# sensortag_motherboard_v004.net
KiCad netlist of a schematic drawn in EAGLE
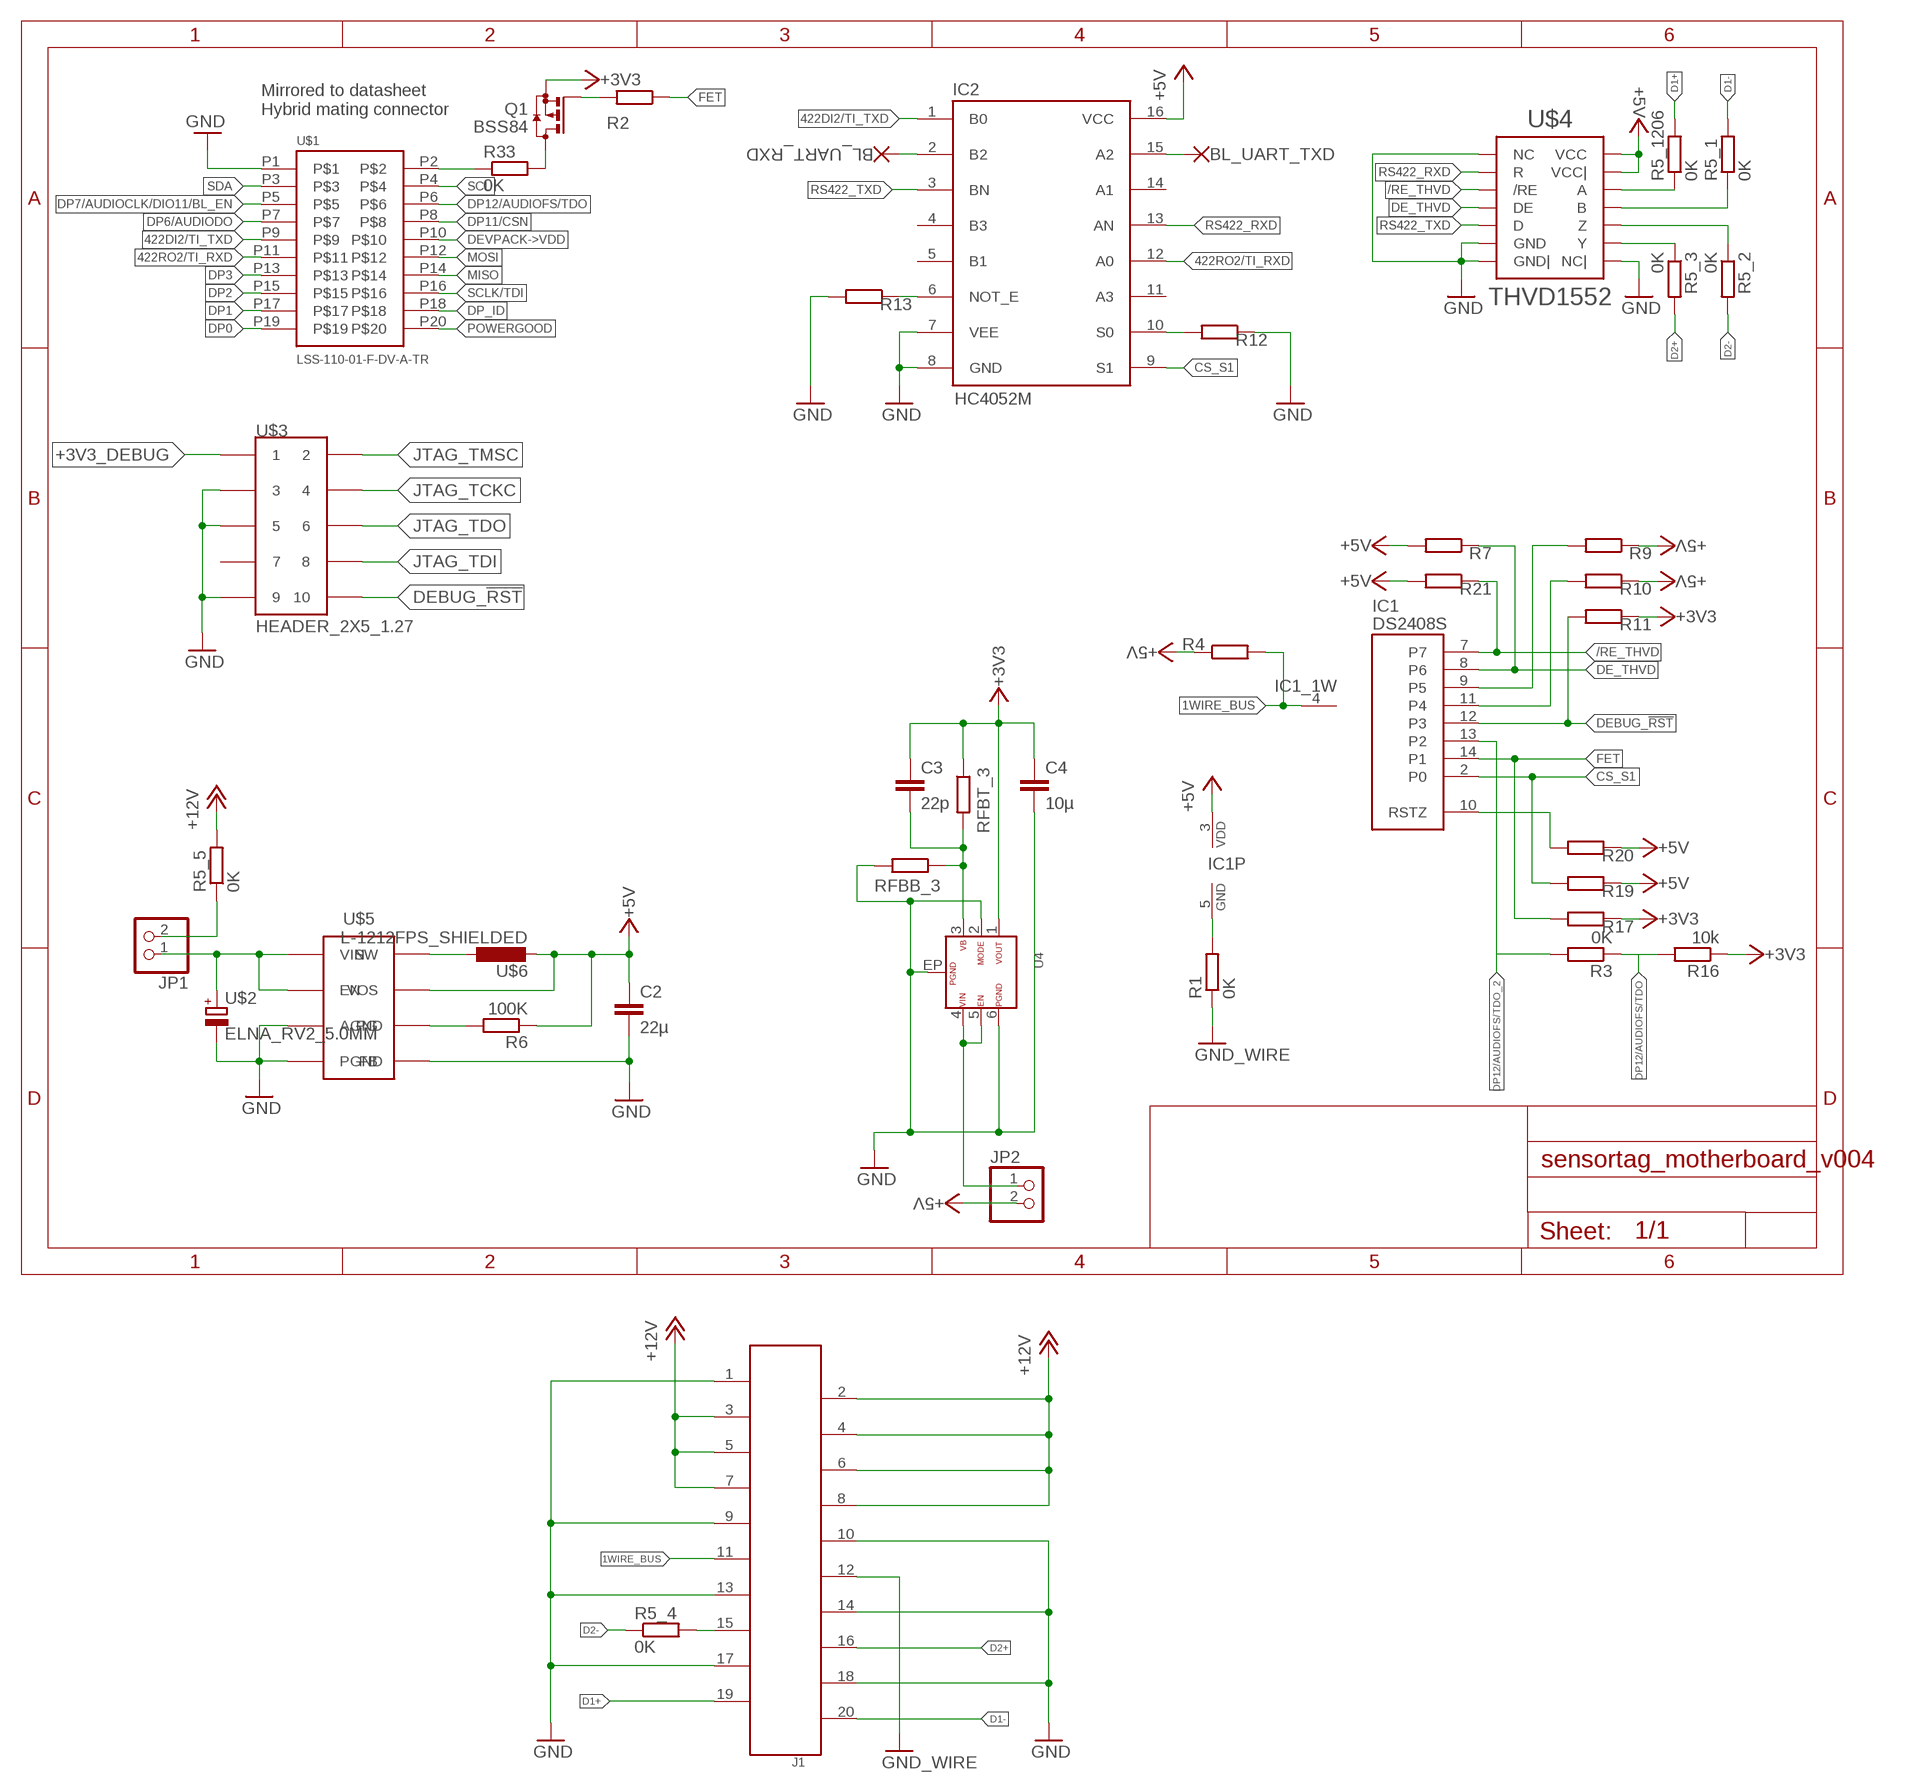
[diagram p0: schematic, sheet 1]

(export (version "E")
  (design (tool "Eeschema 10.0.6"))
  (components
    (comp (ref "BL_UART_RXD")
      (value "WIREPADSMD1,27-254")
      (footprint "eagle-import:SMD1,27-2,54")
      (libsource (lib "eagle-import") (part "WIREPADSMD1,27-254"))
    )
    (comp (ref "BL_UART_TXD")
      (value "WIREPADSMD1,27-254")
      (footprint "eagle-import:SMD1,27-2,54")
      (libsource (lib "eagle-import") (part "WIREPADSMD1,27-254"))
    )
    (comp (ref "C2")
      (value "22µ")
      (footprint "eagle-import:C1206")
      (libsource (lib "eagle-import") (part "C-EUC1206"))
    )
    (comp (ref "C3")
      (value "22p")
      (footprint "eagle-import:C0402")
      (libsource (lib "eagle-import") (part "C-EUC0402"))
    )
    (comp (ref "C4")
      (value "10µ")
      (footprint "eagle-import:C0603")
      (libsource (lib "eagle-import") (part "C-EUC0603"))
    )
    (comp (ref "IC1")
      (value "DS2408S")
      (footprint "eagle-import:SO16")
      (libsource (lib "eagle-import") (part "DS2408S"))
    )
    (comp (ref "IC2")
      (value "HC4052M")
      (footprint "eagle-import:SO16")
      (libsource (lib "eagle-import") (part "HC4052M"))
    )
    (comp (ref "J1")
      (value "490107672012")
      (footprint "eagle-import:490107672012")
      (libsource (lib "eagle-import") (part "490107672012"))
    )
    (comp (ref "JP1")
      (value "PINHD-1X2")
      (footprint "eagle-import:1X02")
      (libsource (lib "eagle-import") (part "PINHD-1X2"))
    )
    (comp (ref "JP2")
      (value "PINHD-1X2")
      (footprint "eagle-import:1X02")
      (libsource (lib "eagle-import") (part "PINHD-1X2"))
    )
    (comp (ref "Q1")
      (value "BSS84")
      (footprint "eagle-import:SOT23")
      (libsource (lib "eagle-import") (part "BSS84"))
    )
    (comp (ref "R1")
      (value "0K")
      (footprint "eagle-import:R0603")
      (libsource (lib "eagle-import") (part "R-EU_R0603"))
    )
    (comp (ref "R2")
      (value "100")
      (footprint "eagle-import:R0402")
      (libsource (lib "eagle-import") (part "R0402"))
    )
    (comp (ref "R3")
      (value "0K")
      (footprint "eagle-import:R0603")
      (libsource (lib "eagle-import") (part "R-EU_R0603"))
    )
    (comp (ref "R4")
      (value "10k")
      (footprint "eagle-import:R0402")
      (libsource (lib "eagle-import") (part "R0402"))
    )
    (comp (ref "R5_1")
      (value "0K")
      (footprint "eagle-import:R1206")
      (libsource (lib "eagle-import") (part "R-EU_R1206"))
    )
    (comp (ref "R5_2")
      (value "0K")
      (footprint "eagle-import:R1206")
      (libsource (lib "eagle-import") (part "R-EU_R1206"))
    )
    (comp (ref "R5_3")
      (value "0K")
      (footprint "eagle-import:R1206")
      (libsource (lib "eagle-import") (part "R-EU_R1206"))
    )
    (comp (ref "R5_4")
      (value "0K")
      (footprint "eagle-import:R1206")
      (libsource (lib "eagle-import") (part "R-EU_R1206"))
    )
    (comp (ref "R5_5")
      (value "0K")
      (footprint "eagle-import:R1206")
      (libsource (lib "eagle-import") (part "R-EU_R1206"))
    )
    (comp (ref "R5_1206")
      (value "0K")
      (footprint "eagle-import:R1206")
      (libsource (lib "eagle-import") (part "R-EU_R1206"))
    )
    (comp (ref "R6")
      (value "100K")
      (footprint "eagle-import:R0603")
      (libsource (lib "eagle-import") (part "R-EU_R0603"))
    )
    (comp (ref "R7")
      (value "10k")
      (footprint "eagle-import:R0402")
      (libsource (lib "eagle-import") (part "R0402"))
    )
    (comp (ref "R9")
      (value "10k")
      (footprint "eagle-import:R0402")
      (libsource (lib "eagle-import") (part "R0402"))
    )
    (comp (ref "R10")
      (value "10k")
      (footprint "eagle-import:R0402")
      (libsource (lib "eagle-import") (part "R0402"))
    )
    (comp (ref "R11")
      (value "10k")
      (footprint "eagle-import:R0402")
      (libsource (lib "eagle-import") (part "R0402"))
    )
    (comp (ref "R12")
      (value "10k")
      (footprint "eagle-import:R0402")
      (libsource (lib "eagle-import") (part "R0402"))
    )
    (comp (ref "R13")
      (value "10k")
      (footprint "eagle-import:R0402")
      (libsource (lib "eagle-import") (part "R0402"))
    )
    (comp (ref "R16")
      (value "10k")
      (footprint "eagle-import:R0402")
      (libsource (lib "eagle-import") (part "R0402"))
    )
    (comp (ref "R17")
      (value "10k")
      (footprint "eagle-import:R0402")
      (libsource (lib "eagle-import") (part "R0402"))
    )
    (comp (ref "R19")
      (value "10k")
      (footprint "eagle-import:R0402")
      (libsource (lib "eagle-import") (part "R0402"))
    )
    (comp (ref "R20")
      (value "10k")
      (footprint "eagle-import:R0402")
      (libsource (lib "eagle-import") (part "R0402"))
    )
    (comp (ref "R21")
      (value "10k")
      (footprint "eagle-import:R0402")
      (libsource (lib "eagle-import") (part "R0402"))
    )
    (comp (ref "R33")
      (value "0K")
      (footprint "eagle-import:R0603")
      (libsource (lib "eagle-import") (part "R-EU_R0603"))
    )
    (comp (ref "RFBB_3")
      (value "22,1K")
      (footprint "eagle-import:R0402")
      (libsource (lib "eagle-import") (part "R0402"))
    )
    (comp (ref "RFBT_3")
      (value "100K")
      (footprint "eagle-import:R0402")
      (libsource (lib "eagle-import") (part "R0402"))
    )
    (comp (ref "U$1")
      (value "LSS-110-01-F-DV-A-TR")
      (footprint "eagle-import:LSS-110-01-F-DV-A-TR")
      (libsource (lib "eagle-import") (part "LSS-110-01-F-DV-A-TR"))
    )
    (comp (ref "U$2")
      (value "ELNA_RV2_5.0MM")
      (footprint "eagle-import:ELNA_RV2_5.0MM")
      (libsource (lib "eagle-import") (part "ELNA_RV2_5.0MM"))
    )
    (comp (ref "U$3")
      (value "HEADER_2X5_1.27")
      (footprint "eagle-import:HEADER_2X5_1.27")
      (libsource (lib "eagle-import") (part "HEADER_2X5_1.27"))
    )
    (comp (ref "U$4")
      (value "TVHD1552")
      (footprint "eagle-import:SO14")
      (libsource (lib "eagle-import") (part "TVHD1552"))
    )
    (comp (ref "U$5")
      (value "TPS62173")
      (footprint "eagle-import:WSON8")
      (libsource (lib "eagle-import") (part "TPS62173"))
    )
    (comp (ref "U$6")
      (value "L-1212FPS_SHIELDED")
      (footprint "eagle-import:L-1212FPS_SHIELDED")
      (libsource (lib "eagle-import") (part "L-1212FPS_SHIELDED"))
    )
    (comp (ref "U4")
      (value "VDMM_171960501")
      (footprint "eagle-import:VDMM_171960501")
      (libsource (lib "eagle-import") (part "VDMM_171960501"))
    )
  )
  (nets
    (net (code "1") (name "+3V3") (class "Default")
      (node (ref "C3") (pin "1") (pinfunction "1_1") (pintype "passive"))
      (node (ref "C4") (pin "1") (pinfunction "1_1") (pintype "passive"))
      (node (ref "Q1") (pin "2") (pinfunction "S_2") (pintype "passive"))
      (node (ref "R11") (pin "P$1") (pinfunction "1_P$1") (pintype "passive"))
      (node (ref "R16") (pin "P$1") (pinfunction "1_P$1") (pintype "passive"))
      (node (ref "R17") (pin "P$1") (pinfunction "1_P$1") (pintype "passive"))
      (node (ref "RFBT_3") (pin "P$1") (pinfunction "1_P$1") (pintype "passive"))
      (node (ref "U4") (pin "1") (pinfunction "VOUT_1") (pintype "output"))
    )
    (net (code "2") (name "+3V3_DEBUG") (class "Default")
      (node (ref "U$3") (pin "P$1") (pinfunction "1_P$1") (pintype "bidirectional"))
    )
    (net (code "3") (name "+5V") (class "Default")
      (node (ref "C2") (pin "1") (pinfunction "1_1") (pintype "passive"))
      (node (ref "IC1") (pin "3") (pinfunction "VDD_3") (pintype "power_in"))
      (node (ref "IC2") (pin "16") (pinfunction "VCC_16") (pintype "bidirectional"))
      (node (ref "JP2") (pin "2") (pinfunction "2_2") (pintype "passive"))
      (node (ref "R10") (pin "P$1") (pinfunction "1_P$1") (pintype "passive"))
      (node (ref "R19") (pin "P$1") (pinfunction "1_P$1") (pintype "passive"))
      (node (ref "R20") (pin "P$1") (pinfunction "1_P$1") (pintype "passive"))
      (node (ref "R21") (pin "P$2") (pinfunction "2_P$2") (pintype "passive"))
      (node (ref "R4") (pin "P$1") (pinfunction "1_P$1") (pintype "passive"))
      (node (ref "R6") (pin "1") (pinfunction "1_1") (pintype "passive"))
      (node (ref "R7") (pin "P$2") (pinfunction "2_P$2") (pintype "passive"))
      (node (ref "R9") (pin "P$1") (pinfunction "1_P$1") (pintype "passive"))
      (node (ref "U$4") (pin "13") (pinfunction "VCC|_13") (pintype "bidirectional"))
      (node (ref "U$4") (pin "14") (pinfunction "VCC_14") (pintype "bidirectional"))
      (node (ref "U$5") (pin "VOS") (pinfunction "VOS_VOS") (pintype "bidirectional"))
      (node (ref "U$6") (pin "P$2") (pinfunction "2_P$2") (pintype "passive"))
    )
    (net (code "4") (name "+12V") (class "Default")
      (node (ref "J1") (pin "2") (pinfunction "19_2") (pintype "passive"))
      (node (ref "J1") (pin "3") (pinfunction "18_3") (pintype "passive"))
      (node (ref "J1") (pin "4") (pinfunction "17_4") (pintype "passive"))
      (node (ref "J1") (pin "5") (pinfunction "16_5") (pintype "passive"))
      (node (ref "J1") (pin "6") (pinfunction "15_6") (pintype "passive"))
      (node (ref "J1") (pin "7") (pinfunction "14_7") (pintype "passive"))
      (node (ref "J1") (pin "8") (pinfunction "13_8") (pintype "passive"))
      (node (ref "R5_5") (pin "2") (pinfunction "2_2") (pintype "passive"))
    )
    (net (code "5") (name "/DEBUG_~{RST}") (class "Default")
      (node (ref "IC1") (pin "12") (pinfunction "P3_12") (pintype "open_collector"))
      (node (ref "R11") (pin "P$2") (pinfunction "2_P$2") (pintype "passive"))
      (node (ref "U$3") (pin "P$10") (pinfunction "10_P$10") (pintype "bidirectional"))
    )
    (net (code "6") (name "1WIRE_BUS") (class "Default")
      (node (ref "IC1") (pin "4") (pinfunction "1W_4") (pintype "power_in"))
      (node (ref "J1") (pin "11") (pinfunction "10_11") (pintype "passive"))
      (node (ref "R4") (pin "P$2") (pinfunction "2_P$2") (pintype "passive"))
    )
    (net (code "7") (name "422DI2{slash}TI_TXD") (class "Default")
      (node (ref "IC2") (pin "1") (pinfunction "B0_1") (pintype "bidirectional"))
      (node (ref "U$1") (pin "P9") (pinfunction "P$9_P9") (pintype "bidirectional"))
    )
    (net (code "8") (name "422RO2{slash}TI_RXD") (class "Default")
      (node (ref "IC2") (pin "12") (pinfunction "A0_12") (pintype "bidirectional"))
      (node (ref "U$1") (pin "P11") (pinfunction "P$11_P11") (pintype "bidirectional"))
    )
    (net (code "9") (name "CS_S1") (class "Default")
      (node (ref "IC1") (pin "2") (pinfunction "P0_2") (pintype "open_collector"))
      (node (ref "IC2") (pin "9") (pinfunction "S1_9") (pintype "bidirectional"))
      (node (ref "R19") (pin "P$2") (pinfunction "2_P$2") (pintype "passive"))
    )
    (net (code "10") (name "D1+") (class "Default")
      (node (ref "J1") (pin "19") (pinfunction "2_19") (pintype "passive"))
      (node (ref "R5_1206") (pin "2") (pinfunction "2_2") (pintype "passive"))
    )
    (net (code "11") (name "D1-") (class "Default")
      (node (ref "J1") (pin "20") (pinfunction "1_20") (pintype "passive"))
      (node (ref "R5_1") (pin "2") (pinfunction "2_2") (pintype "passive"))
    )
    (net (code "12") (name "D2+") (class "Default")
      (node (ref "J1") (pin "16") (pinfunction "5_16") (pintype "passive"))
      (node (ref "R5_3") (pin "2") (pinfunction "2_2") (pintype "passive"))
    )
    (net (code "13") (name "D2-") (class "Default")
      (node (ref "R5_2") (pin "2") (pinfunction "2_2") (pintype "passive"))
      (node (ref "R5_4") (pin "1") (pinfunction "1_1") (pintype "passive"))
    )
    (net (code "14") (name "DEVPACK->VDD") (class "Default")
      (node (ref "U$1") (pin "P10") (pinfunction "P$10_P10") (pintype "bidirectional"))
    )
    (net (code "15") (name "DE_THVD") (class "Default")
      (node (ref "IC1") (pin "8") (pinfunction "P6_8") (pintype "open_collector"))
      (node (ref "R7") (pin "P$1") (pinfunction "1_P$1") (pintype "passive"))
      (node (ref "U$4") (pin "4") (pinfunction "DE_4") (pintype "bidirectional"))
    )
    (net (code "16") (name "DP0") (class "Default")
      (node (ref "U$1") (pin "P19") (pinfunction "P$19_P19") (pintype "bidirectional"))
    )
    (net (code "17") (name "DP1") (class "Default")
      (node (ref "U$1") (pin "P17") (pinfunction "P$17_P17") (pintype "bidirectional"))
    )
    (net (code "18") (name "DP2") (class "Default")
      (node (ref "U$1") (pin "P15") (pinfunction "P$15_P15") (pintype "bidirectional"))
    )
    (net (code "19") (name "DP3") (class "Default")
      (node (ref "U$1") (pin "P13") (pinfunction "P$13_P13") (pintype "bidirectional"))
    )
    (net (code "20") (name "DP6{slash}AUDIODO") (class "Default")
      (node (ref "U$1") (pin "P7") (pinfunction "P$7_P7") (pintype "bidirectional"))
    )
    (net (code "21") (name "DP7{slash}AUDIOCLK{slash}DIO11{slash}BL_EN") (class "Default")
      (node (ref "U$1") (pin "P5") (pinfunction "P$5_P5") (pintype "bidirectional"))
    )
    (net (code "22") (name "DP11{slash}CSN") (class "Default")
      (node (ref "U$1") (pin "P8") (pinfunction "P$8_P8") (pintype "bidirectional"))
    )
    (net (code "23") (name "DP12{slash}AUDIOFS{slash}TDO") (class "Default")
      (node (ref "R16") (pin "P$2") (pinfunction "2_P$2") (pintype "passive"))
      (node (ref "R3") (pin "1") (pinfunction "1_1") (pintype "passive"))
      (node (ref "U$1") (pin "P6") (pinfunction "P$6_P6") (pintype "bidirectional"))
    )
    (net (code "24") (name "DP12{slash}AUDIOFS{slash}TDO_2") (class "Default")
      (node (ref "IC1") (pin "13") (pinfunction "P2_13") (pintype "open_collector"))
      (node (ref "R3") (pin "2") (pinfunction "2_2") (pintype "passive"))
    )
    (net (code "25") (name "DP_ID") (class "Default")
      (node (ref "U$1") (pin "P18") (pinfunction "P$18_P18") (pintype "bidirectional"))
    )
    (net (code "26") (name "FET") (class "Default")
      (node (ref "IC1") (pin "14") (pinfunction "P1_14") (pintype "open_collector"))
      (node (ref "R17") (pin "P$2") (pinfunction "2_P$2") (pintype "passive"))
      (node (ref "R2") (pin "P$1") (pinfunction "1_P$1") (pintype "passive"))
    )
    (net (code "27") (name "GND") (class "Default")
      (node (ref "C2") (pin "2") (pinfunction "2_2") (pintype "passive"))
      (node (ref "C4") (pin "2") (pinfunction "2_2") (pintype "passive"))
      (node (ref "IC2") (pin "7") (pinfunction "VEE_7") (pintype "bidirectional"))
      (node (ref "IC2") (pin "8") (pinfunction "GND_8") (pintype "bidirectional"))
      (node (ref "J1") (pin "1") (pinfunction "20_1") (pintype "passive"))
      (node (ref "J1") (pin "10") (pinfunction "11_10") (pintype "passive"))
      (node (ref "J1") (pin "13") (pinfunction "8_13") (pintype "passive"))
      (node (ref "J1") (pin "14") (pinfunction "7_14") (pintype "passive"))
      (node (ref "J1") (pin "17") (pinfunction "4_17") (pintype "passive"))
      (node (ref "J1") (pin "18") (pinfunction "3_18") (pintype "passive"))
      (node (ref "J1") (pin "9") (pinfunction "12_9") (pintype "passive"))
      (node (ref "R12") (pin "P$1") (pinfunction "1_P$1") (pintype "passive"))
      (node (ref "R13") (pin "P$2") (pinfunction "2_P$2") (pintype "passive"))
      (node (ref "RFBB_3") (pin "P$2") (pinfunction "2_P$2") (pintype "passive"))
      (node (ref "U$1") (pin "P1") (pinfunction "P$1_P1") (pintype "bidirectional"))
      (node (ref "U$2") (pin "P-") (pinfunction "-_P-") (pintype "passive"))
      (node (ref "U$3") (pin "P$3") (pinfunction "3_P$3") (pintype "bidirectional"))
      (node (ref "U$3") (pin "P$5") (pinfunction "5_P$5") (pintype "bidirectional"))
      (node (ref "U$3") (pin "P$9") (pinfunction "9_P$9") (pintype "bidirectional"))
      (node (ref "U$4") (pin "1") (pinfunction "NC_1") (pintype "bidirectional"))
      (node (ref "U$4") (pin "6") (pinfunction "GND_6") (pintype "bidirectional"))
      (node (ref "U$4") (pin "7") (pinfunction "GND|_7") (pintype "bidirectional"))
      (node (ref "U$4") (pin "8") (pinfunction "NC|_8") (pintype "bidirectional"))
      (node (ref "U$5") (pin "AGND") (pinfunction "AGND_AGND") (pintype "bidirectional"))
      (node (ref "U$5") (pin "AGND2") (pinfunction "AGND_AGND2") (pintype "bidirectional"))
      (node (ref "U$5") (pin "FB") (pinfunction "FB_FB") (pintype "bidirectional"))
      (node (ref "U$5") (pin "PGND") (pinfunction "PGND_PGND") (pintype "bidirectional"))
      (node (ref "U4") (pin "2") (pinfunction "MODE_2") (pintype "bidirectional"))
      (node (ref "U4") (pin "6") (pinfunction "PGND_6") (pintype "bidirectional"))
      (node (ref "U4") (pin "EP") (pinfunction "PGND1_EP") (pintype "bidirectional"))
    )
    (net (code "28") (name "GND_WIRE") (class "Default")
      (node (ref "J1") (pin "12") (pinfunction "9_12") (pintype "passive"))
      (node (ref "R1") (pin "1") (pinfunction "1_1") (pintype "passive"))
    )
    (net (code "29") (name "JTAG_TCKC") (class "Default")
      (node (ref "U$3") (pin "P$4") (pinfunction "4_P$4") (pintype "bidirectional"))
    )
    (net (code "30") (name "JTAG_TDI") (class "Default")
      (node (ref "U$3") (pin "P$8") (pinfunction "8_P$8") (pintype "bidirectional"))
    )
    (net (code "31") (name "JTAG_TDO") (class "Default")
      (node (ref "U$3") (pin "P$6") (pinfunction "6_P$6") (pintype "bidirectional"))
    )
    (net (code "32") (name "JTAG_TMSC") (class "Default")
      (node (ref "U$3") (pin "P$2") (pinfunction "2_P$2") (pintype "bidirectional"))
    )
    (net (code "33") (name "MISO") (class "Default")
      (node (ref "U$1") (pin "P14") (pinfunction "P$14_P14") (pintype "bidirectional"))
    )
    (net (code "34") (name "MOSI") (class "Default")
      (node (ref "U$1") (pin "P12") (pinfunction "P$12_P12") (pintype "bidirectional"))
    )
    (net (code "35") (name "Net-(BL_UART_RXD-P)") (class "Default")
      (node (ref "BL_UART_RXD") (pin "1") (pinfunction "P_1") (pintype "passive"))
      (node (ref "IC2") (pin "2") (pinfunction "B2_2") (pintype "bidirectional"))
    )
    (net (code "36") (name "Net-(BL_UART_TXD-P)") (class "Default")
      (node (ref "BL_UART_TXD") (pin "1") (pinfunction "P_1") (pintype "passive"))
      (node (ref "IC2") (pin "15") (pinfunction "A2_15") (pintype "bidirectional"))
    )
    (net (code "37") (name "Net-(IC1A-P4)") (class "Default")
      (node (ref "IC1") (pin "11") (pinfunction "P4_11") (pintype "open_collector"))
      (node (ref "R10") (pin "P$2") (pinfunction "2_P$2") (pintype "passive"))
    )
    (net (code "38") (name "Net-(IC1A-P5)") (class "Default")
      (node (ref "IC1") (pin "9") (pinfunction "P5_9") (pintype "open_collector"))
      (node (ref "R9") (pin "P$2") (pinfunction "2_P$2") (pintype "passive"))
    )
    (net (code "39") (name "Net-(IC1A-RSTZ)") (class "Default")
      (node (ref "IC1") (pin "10") (pinfunction "RSTZ_10") (pintype "open_collector"))
      (node (ref "R20") (pin "P$2") (pinfunction "2_P$2") (pintype "passive"))
    )
    (net (code "40") (name "Net-(IC1B-GND)") (class "Default")
      (node (ref "IC1") (pin "5") (pinfunction "GND_5") (pintype "power_in"))
      (node (ref "R1") (pin "2") (pinfunction "2_2") (pintype "passive"))
    )
    (net (code "41") (name "Net-(IC2-NOT_E)") (class "Default")
      (node (ref "IC2") (pin "6") (pinfunction "NOT_E_6") (pintype "bidirectional"))
      (node (ref "R13") (pin "P$1") (pinfunction "1_P$1") (pintype "passive"))
    )
    (net (code "42") (name "Net-(IC2-S0)") (class "Default")
      (node (ref "IC2") (pin "10") (pinfunction "S0_10") (pintype "bidirectional"))
      (node (ref "R12") (pin "P$2") (pinfunction "2_P$2") (pintype "passive"))
    )
    (net (code "43") (name "Net-(J1-6)") (class "Default")
      (node (ref "J1") (pin "15") (pinfunction "6_15") (pintype "passive"))
      (node (ref "R5_4") (pin "2") (pinfunction "2_2") (pintype "passive"))
    )
    (net (code "44") (name "Net-(JP1-Pad2)") (class "Default")
      (node (ref "JP1") (pin "2") (pinfunction "2_2") (pintype "passive"))
      (node (ref "R5_5") (pin "1") (pinfunction "1_1") (pintype "passive"))
    )
    (net (code "45") (name "Net-(Q1-D)") (class "Default")
      (node (ref "Q1") (pin "3") (pinfunction "D_3") (pintype "passive"))
      (node (ref "R33") (pin "2") (pinfunction "2_2") (pintype "passive"))
    )
    (net (code "46") (name "Net-(Q1-G)") (class "Default")
      (node (ref "Q1") (pin "1") (pinfunction "G_1") (pintype "passive"))
      (node (ref "R2") (pin "P$2") (pinfunction "2_P$2") (pintype "passive"))
    )
    (net (code "47") (name "Net-(R6-Pad2)") (class "Default")
      (node (ref "R6") (pin "2") (pinfunction "2_2") (pintype "passive"))
      (node (ref "U$5") (pin "PG") (pinfunction "PG_PG") (pintype "bidirectional"))
    )
    (net (code "48") (name "Net-(RFBB_3-1)") (class "Default")
      (node (ref "C3") (pin "2") (pinfunction "2_2") (pintype "passive"))
      (node (ref "RFBB_3") (pin "P$1") (pinfunction "1_P$1") (pintype "passive"))
      (node (ref "RFBT_3") (pin "P$2") (pinfunction "2_P$2") (pintype "passive"))
      (node (ref "U4") (pin "3") (pinfunction "FB_3") (pintype "bidirectional"))
    )
    (net (code "49") (name "Net-(U$1-P$2)") (class "Default")
      (node (ref "R33") (pin "1") (pinfunction "1_1") (pintype "passive"))
      (node (ref "U$1") (pin "P2") (pinfunction "P$2_P2") (pintype "bidirectional"))
    )
    (net (code "50") (name "Net-(U$2-+)") (class "Default")
      (node (ref "JP1") (pin "1") (pinfunction "1_1") (pintype "passive"))
      (node (ref "U$2") (pin "P+") (pinfunction "+_P+") (pintype "passive"))
      (node (ref "U$5") (pin "EN") (pinfunction "EN_EN") (pintype "bidirectional"))
      (node (ref "U$5") (pin "VIN") (pinfunction "VIN_VIN") (pintype "bidirectional"))
    )
    (net (code "51") (name "Net-(U$4-A)") (class "Default")
      (node (ref "R5_1206") (pin "1") (pinfunction "1_1") (pintype "passive"))
      (node (ref "U$4") (pin "12") (pinfunction "A_12") (pintype "bidirectional"))
    )
    (net (code "52") (name "Net-(U$4-B)") (class "Default")
      (node (ref "R5_1") (pin "1") (pinfunction "1_1") (pintype "passive"))
      (node (ref "U$4") (pin "11") (pinfunction "B_11") (pintype "bidirectional"))
    )
    (net (code "53") (name "Net-(U$4-Y)") (class "Default")
      (node (ref "R5_3") (pin "1") (pinfunction "1_1") (pintype "passive"))
      (node (ref "U$4") (pin "9") (pinfunction "Y_9") (pintype "bidirectional"))
    )
    (net (code "54") (name "Net-(U$4-Z)") (class "Default")
      (node (ref "R5_2") (pin "1") (pinfunction "1_1") (pintype "passive"))
      (node (ref "U$4") (pin "10") (pinfunction "Z_10") (pintype "bidirectional"))
    )
    (net (code "55") (name "Net-(U$6-1)") (class "Default")
      (node (ref "U$5") (pin "SW") (pinfunction "SW_SW") (pintype "bidirectional"))
      (node (ref "U$6") (pin "P$1") (pinfunction "1_P$1") (pintype "passive"))
    )
    (net (code "56") (name "Net-(U4-EN)") (class "Default")
      (node (ref "JP2") (pin "1") (pinfunction "1_1") (pintype "passive"))
      (node (ref "U4") (pin "4") (pinfunction "VIN_4") (pintype "input"))
      (node (ref "U4") (pin "5") (pinfunction "EN_5") (pintype "bidirectional"))
    )
    (net (code "57") (name "POWERGOOD") (class "Default")
      (node (ref "U$1") (pin "P20") (pinfunction "P$20_P20") (pintype "bidirectional"))
    )
    (net (code "58") (name "RS422_RXD") (class "Default")
      (node (ref "IC2") (pin "13") (pinfunction "AN_13") (pintype "bidirectional"))
      (node (ref "U$4") (pin "2") (pinfunction "R_2") (pintype "bidirectional"))
    )
    (net (code "59") (name "RS422_TXD") (class "Default")
      (node (ref "IC2") (pin "3") (pinfunction "BN_3") (pintype "bidirectional"))
      (node (ref "U$4") (pin "5") (pinfunction "D_5") (pintype "bidirectional"))
    )
    (net (code "60") (name "SCL") (class "Default")
      (node (ref "U$1") (pin "P4") (pinfunction "P$4_P4") (pintype "bidirectional"))
    )
    (net (code "61") (name "SCLK{slash}TDI") (class "Default")
      (node (ref "U$1") (pin "P16") (pinfunction "P$16_P16") (pintype "bidirectional"))
    )
    (net (code "62") (name "SDA") (class "Default")
      (node (ref "U$1") (pin "P3") (pinfunction "P$3_P3") (pintype "bidirectional"))
    )
    (net (code "63") (name "unconnected-(IC2-A1-Pad14)") (class "Default")
      (node (ref "IC2") (pin "14") (pinfunction "A1_14") (pintype "bidirectional"))
    )
    (net (code "64") (name "unconnected-(IC2-A3-Pad11)") (class "Default")
      (node (ref "IC2") (pin "11") (pinfunction "A3_11") (pintype "bidirectional"))
    )
    (net (code "65") (name "unconnected-(IC2-B1-Pad5)") (class "Default")
      (node (ref "IC2") (pin "5") (pinfunction "B1_5") (pintype "bidirectional"))
    )
    (net (code "66") (name "unconnected-(IC2-B3-Pad4)") (class "Default")
      (node (ref "IC2") (pin "4") (pinfunction "B3_4") (pintype "bidirectional"))
    )
    (net (code "67") (name "unconnected-(U$3-7-PadP$7)") (class "Default")
      (node (ref "U$3") (pin "P$7") (pinfunction "7_P$7") (pintype "bidirectional"))
    )
    (net (code "68") (name "{slash}RE_THVD") (class "Default")
      (node (ref "IC1") (pin "7") (pinfunction "P7_7") (pintype "open_collector"))
      (node (ref "R21") (pin "P$1") (pinfunction "1_P$1") (pintype "passive"))
      (node (ref "U$4") (pin "3") (pinfunction "/RE_3") (pintype "bidirectional"))
    )
  )
)
